# DoXe_7SEG_Arduino.net
KiCad netlist of a schematic drawn in Altium Designer
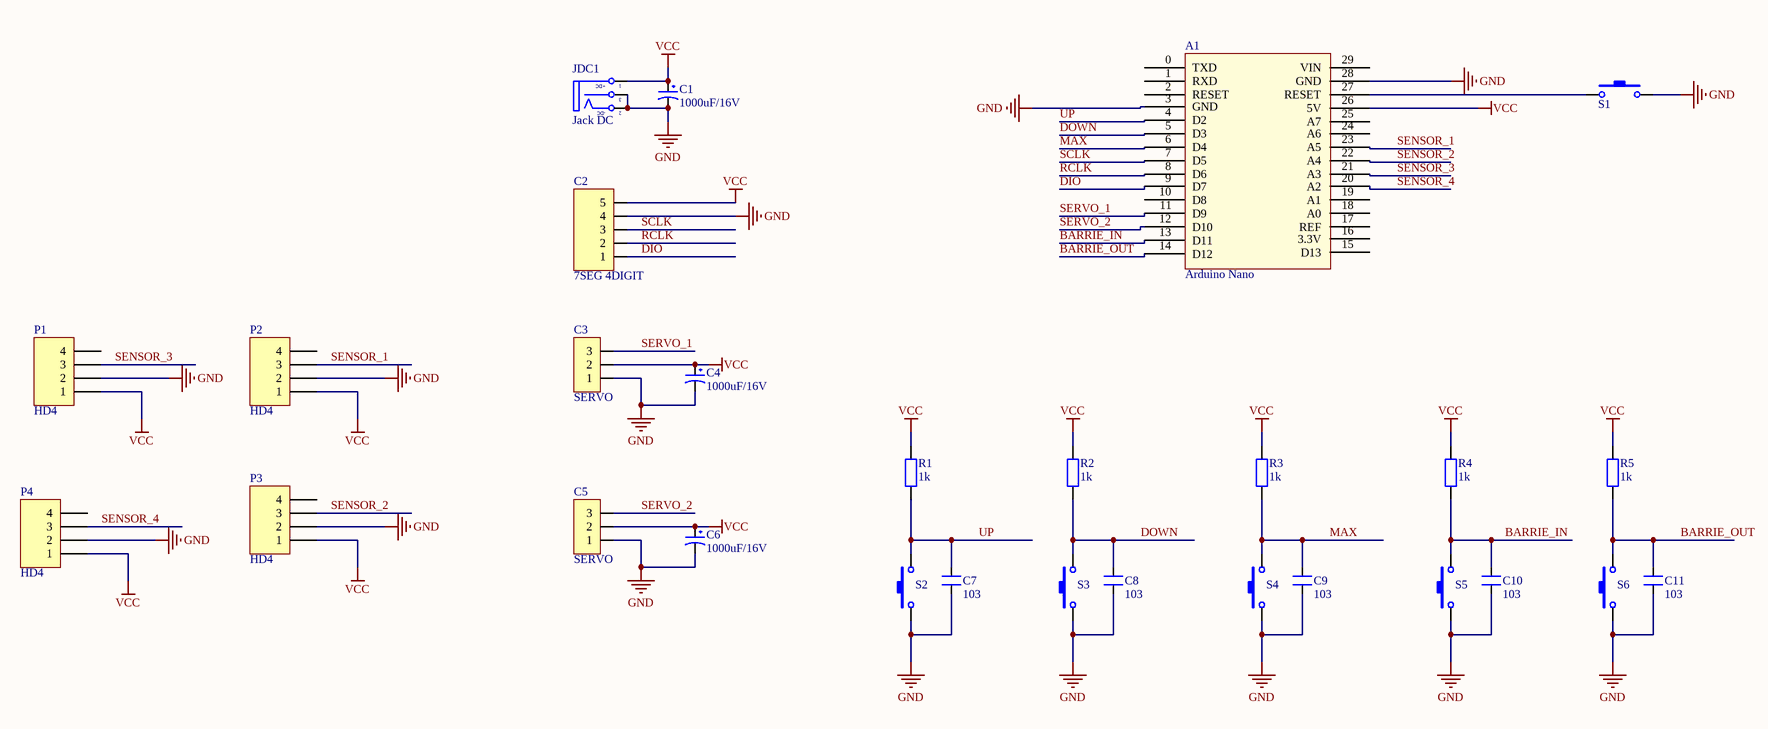
[diagram p0: DoXe_7SEG_Arduino.SchDoc]

(export (version "E")
  (design (tool "Eeschema 10.0.6"))
  (components
    (comp (ref "A1")
      (value "Arduino Nano")
      (footprint "Arduino Nano_JUMP")
      (libsource (lib "OBIT_TESLA") (part "Arduino Nano"))
    )
    (comp (ref "C1")
      (value "1000uF/16V")
      (footprint "CP1.5/3.4")
      (description "Cap 1000uF/16V - 220uF/50V")
      (libsource (lib "OBIT_TESLA") (part "CP4"))
    )
    (comp (ref "C2")
      (value "7SEG 4DIGIT")
      (footprint "JP5-D1T")
      (description "WR-PHD 2.54 mm Angled Socket Header")
      (fields
        (field (name "MANUFACTURER") "Würth Elektronik eiSos GmbH")
        (field (name "PARTNO") "613005143121")
        (field (name "CREATED BY") "Karrer Zheng")
      )
      (libsource (lib "OBIT_TESLA") (part "JP5"))
    )
    (comp (ref "C3")
      (value "SERVO")
      (footprint "JP3-D1T")
      (description "WR-PHD 2.54 mm Angled Socket Header")
      (fields
        (field (name "MANUFACTURER") "Würth Elektronik eiSos GmbH")
        (field (name "PARTNO") "613003143121")
        (field (name "CREATED BY") "Karrer Zheng")
      )
      (libsource (lib "OBIT_TESLA") (part "JP3"))
    )
    (comp (ref "C4")
      (value "1000uF/16V")
      (footprint "CP1.5/3.4")
      (description "Cap 1000uF/16V - 220uF/50V")
      (libsource (lib "OBIT_TESLA") (part "CP4"))
    )
    (comp (ref "C5")
      (value "SERVO")
      (footprint "JP3-D1T")
      (description "WR-PHD 2.54 mm Angled Socket Header")
      (fields
        (field (name "MANUFACTURER") "Würth Elektronik eiSos GmbH")
        (field (name "PARTNO") "613003143121")
        (field (name "CREATED BY") "Karrer Zheng")
      )
      (libsource (lib "OBIT_TESLA") (part "JP3"))
    )
    (comp (ref "C6")
      (value "1000uF/16V")
      (footprint "CP1.5/3.4")
      (description "Cap 1000uF/16V - 220uF/50V")
      (libsource (lib "OBIT_TESLA") (part "CP4"))
    )
    (comp (ref "C7")
      (value "103")
      (footprint "SM-0805")
      (description "Cap SMD")
      (libsource (lib "OBIT_TESLA") (part "CM"))
    )
    (comp (ref "C8")
      (value "103")
      (footprint "SM-0805")
      (description "Cap SMD")
      (libsource (lib "OBIT_TESLA") (part "CM"))
    )
    (comp (ref "C9")
      (value "103")
      (footprint "SM-0805")
      (description "Cap SMD")
      (libsource (lib "OBIT_TESLA") (part "CM"))
    )
    (comp (ref "C10")
      (value "103")
      (footprint "SM-0805")
      (description "Cap SMD")
      (libsource (lib "OBIT_TESLA") (part "CM"))
    )
    (comp (ref "C11")
      (value "103")
      (footprint "SM-0805")
      (description "Cap SMD")
      (libsource (lib "OBIT_TESLA") (part "CM"))
    )
    (comp (ref "JDC1") (value "Jack DC") (footprint "DC0") (libsource (lib "OBIT_TESLA") (part "JACK_DC")))
    (comp (ref "P1") (value "HD4") (footprint "HEADER 4") (libsource (lib "OBIT_TESLA") (part "HEADER 4")))
    (comp (ref "P2") (value "HD4") (footprint "HEADER 4") (libsource (lib "OBIT_TESLA") (part "HEADER 4")))
    (comp (ref "P3") (value "HD4") (footprint "HEADER 4") (libsource (lib "OBIT_TESLA") (part "HEADER 4")))
    (comp (ref "P4") (value "HD4") (footprint "HEADER 4") (libsource (lib "OBIT_TESLA") (part "HEADER 4")))
    (comp (ref "R1")
      (value "1k")
      (footprint "RES-1/4W")
      (description "Resistor R1/4W")
      (libsource (lib "OBIT_TESLA") (part "R"))
    )
    (comp (ref "R2")
      (value "1k")
      (footprint "RES-1/4W")
      (description "Resistor R1/4W")
      (libsource (lib "OBIT_TESLA") (part "R"))
    )
    (comp (ref "R3")
      (value "1k")
      (footprint "RES-1/4W")
      (description "Resistor R1/4W")
      (libsource (lib "OBIT_TESLA") (part "R"))
    )
    (comp (ref "R4")
      (value "1k")
      (footprint "RES-1/4W")
      (description "Resistor R1/4W")
      (libsource (lib "OBIT_TESLA") (part "R"))
    )
    (comp (ref "R5")
      (value "1k")
      (footprint "RES-1/4W")
      (description "Resistor R1/4W")
      (libsource (lib "OBIT_TESLA") (part "R"))
    )
    (comp (ref "S1")
      (value "SW")
      (footprint "BUTTON  ROUND")
      (description "Switch-Button")
      (fields (field (name "PUBLISHER") "Altium Limited"))
      (libsource (lib "OBIT_TESLA") (part "SW-Button"))
    )
    (comp (ref "S2")
      (value "SW")
      (footprint "BUTTON  ROUND")
      (description "Switch-Button")
      (fields (field (name "PUBLISHER") "Altium Limited"))
      (libsource (lib "OBIT_TESLA") (part "SW-Button"))
    )
    (comp (ref "S3")
      (value "SW")
      (footprint "BUTTON  ROUND")
      (description "Switch-Button")
      (fields (field (name "PUBLISHER") "Altium Limited"))
      (libsource (lib "OBIT_TESLA") (part "SW-Button"))
    )
    (comp (ref "S4")
      (value "SW")
      (footprint "BUTTON  ROUND")
      (description "Switch-Button")
      (fields (field (name "PUBLISHER") "Altium Limited"))
      (libsource (lib "OBIT_TESLA") (part "SW-Button"))
    )
    (comp (ref "S5")
      (value "SW")
      (footprint "BUTTON  ROUND")
      (description "Switch-Button")
      (fields (field (name "PUBLISHER") "Altium Limited"))
      (libsource (lib "OBIT_TESLA") (part "SW-Button"))
    )
    (comp (ref "S6")
      (value "SW")
      (footprint "BUTTON  ROUND")
      (description "Switch-Button")
      (fields (field (name "PUBLISHER") "Altium Limited"))
      (libsource (lib "OBIT_TESLA") (part "SW-Button"))
    )
  )
  (nets
    (net (code "1") (name "/BARRIE_IN") (class "Default")
      (node (ref "A1") (pin "13") (pinfunction "D11_13") (pintype "passive"))
      (node (ref "C10") (pin "2") (pinfunction "2_2") (pintype "passive"))
      (node (ref "R4") (pin "1") (pinfunction "1_1") (pintype "passive"))
      (node (ref "S5") (pin "2") (pinfunction "2_2") (pintype "passive"))
    )
    (net (code "2") (name "/BARRIE_OUT") (class "Default")
      (node (ref "A1") (pin "14") (pinfunction "D12_14") (pintype "passive"))
      (node (ref "C11") (pin "2") (pinfunction "2_2") (pintype "passive"))
      (node (ref "R5") (pin "1") (pinfunction "1_1") (pintype "passive"))
      (node (ref "S6") (pin "2") (pinfunction "2_2") (pintype "passive"))
    )
    (net (code "3") (name "/DIO") (class "Default")
      (node (ref "A1") (pin "9") (pinfunction "D7_9") (pintype "passive"))
      (node (ref "C2") (pin "1") (pinfunction "1_1") (pintype "passive"))
    )
    (net (code "4") (name "/DOWN") (class "Default")
      (node (ref "A1") (pin "5") (pinfunction "D3_5") (pintype "passive"))
      (node (ref "C8") (pin "2") (pinfunction "2_2") (pintype "passive"))
      (node (ref "R2") (pin "1") (pinfunction "1_1") (pintype "passive"))
      (node (ref "S3") (pin "2") (pinfunction "2_2") (pintype "passive"))
    )
    (net (code "5") (name "/MAX") (class "Default")
      (node (ref "A1") (pin "6") (pinfunction "D4_6") (pintype "passive"))
      (node (ref "C9") (pin "2") (pinfunction "2_2") (pintype "passive"))
      (node (ref "R3") (pin "1") (pinfunction "1_1") (pintype "passive"))
      (node (ref "S4") (pin "2") (pinfunction "2_2") (pintype "passive"))
    )
    (net (code "6") (name "/RCLK") (class "Default")
      (node (ref "A1") (pin "8") (pinfunction "D6_8") (pintype "passive"))
      (node (ref "C2") (pin "2") (pinfunction "2_2") (pintype "passive"))
    )
    (net (code "7") (name "/SCLK") (class "Default")
      (node (ref "A1") (pin "7") (pinfunction "D5_7") (pintype "passive"))
      (node (ref "C2") (pin "3") (pinfunction "3_3") (pintype "passive"))
    )
    (net (code "8") (name "/SENSOR_1") (class "Default")
      (node (ref "A1") (pin "23") (pinfunction "A5_23") (pintype "passive"))
      (node (ref "P2") (pin "3") (pinfunction "3_3") (pintype "passive"))
    )
    (net (code "9") (name "/SENSOR_2") (class "Default")
      (node (ref "A1") (pin "22") (pinfunction "A4_22") (pintype "passive"))
      (node (ref "P3") (pin "3") (pinfunction "3_3") (pintype "passive"))
    )
    (net (code "10") (name "/SENSOR_3") (class "Default")
      (node (ref "A1") (pin "21") (pinfunction "A3_21") (pintype "passive"))
      (node (ref "P1") (pin "3") (pinfunction "3_3") (pintype "passive"))
    )
    (net (code "11") (name "/SENSOR_4") (class "Default")
      (node (ref "A1") (pin "20") (pinfunction "A2_20") (pintype "passive"))
      (node (ref "P4") (pin "3") (pinfunction "3_3") (pintype "passive"))
    )
    (net (code "12") (name "/SERVO_1") (class "Default")
      (node (ref "A1") (pin "11") (pinfunction "D9_11") (pintype "passive"))
      (node (ref "C3") (pin "3") (pinfunction "3_3") (pintype "passive"))
    )
    (net (code "13") (name "/SERVO_2") (class "Default")
      (node (ref "A1") (pin "12") (pinfunction "D10_12") (pintype "passive"))
      (node (ref "C5") (pin "3") (pinfunction "3_3") (pintype "passive"))
    )
    (net (code "14") (name "/UP") (class "Default")
      (node (ref "A1") (pin "4") (pinfunction "D2_4") (pintype "passive"))
      (node (ref "C7") (pin "2") (pinfunction "2_2") (pintype "passive"))
      (node (ref "R1") (pin "1") (pinfunction "1_1") (pintype "passive"))
      (node (ref "S2") (pin "2") (pinfunction "2_2") (pintype "passive"))
    )
    (net (code "15") (name "GND") (class "Default")
      (node (ref "A1") (pin "28") (pinfunction "GND_28") (pintype "passive"))
      (node (ref "A1") (pin "3") (pinfunction "GND_3") (pintype "passive"))
      (node (ref "C1") (pin "2") (pinfunction "2_2") (pintype "passive"))
      (node (ref "C10") (pin "1") (pinfunction "1_1") (pintype "passive"))
      (node (ref "C11") (pin "1") (pinfunction "1_1") (pintype "passive"))
      (node (ref "C2") (pin "4") (pinfunction "4_4") (pintype "passive"))
      (node (ref "C3") (pin "1") (pinfunction "1_1") (pintype "passive"))
      (node (ref "C4") (pin "2") (pinfunction "2_2") (pintype "passive"))
      (node (ref "C5") (pin "1") (pinfunction "1_1") (pintype "passive"))
      (node (ref "C6") (pin "2") (pinfunction "2_2") (pintype "passive"))
      (node (ref "C7") (pin "1") (pinfunction "1_1") (pintype "passive"))
      (node (ref "C8") (pin "1") (pinfunction "1_1") (pintype "passive"))
      (node (ref "C9") (pin "1") (pinfunction "1_1") (pintype "passive"))
      (node (ref "JDC1") (pin "2") (pinfunction "TN_2") (pintype "passive"))
      (node (ref "JDC1") (pin "3") (pinfunction "S_3") (pintype "power_in"))
      (node (ref "P1") (pin "2") (pinfunction "2_2") (pintype "passive"))
      (node (ref "P2") (pin "2") (pinfunction "2_2") (pintype "passive"))
      (node (ref "P3") (pin "2") (pinfunction "2_2") (pintype "passive"))
      (node (ref "P4") (pin "2") (pinfunction "2_2") (pintype "passive"))
      (node (ref "S1") (pin "2") (pinfunction "2_2") (pintype "passive"))
      (node (ref "S2") (pin "1") (pinfunction "1_1") (pintype "passive"))
      (node (ref "S3") (pin "1") (pinfunction "1_1") (pintype "passive"))
      (node (ref "S4") (pin "1") (pinfunction "1_1") (pintype "passive"))
      (node (ref "S5") (pin "1") (pinfunction "1_1") (pintype "passive"))
      (node (ref "S6") (pin "1") (pinfunction "1_1") (pintype "passive"))
    )
    (net (code "16") (name "Net-(A1-RESET-Pad27)") (class "Default")
      (node (ref "A1") (pin "27") (pinfunction "RESET_27") (pintype "passive"))
      (node (ref "S1") (pin "1") (pinfunction "1_1") (pintype "passive"))
    )
    (net (code "17") (name "VCC") (class "Default")
      (node (ref "A1") (pin "26") (pinfunction "5V_26") (pintype "passive"))
      (node (ref "C1") (pin "1") (pinfunction "1_1") (pintype "passive"))
      (node (ref "C2") (pin "5") (pinfunction "5_5") (pintype "passive"))
      (node (ref "C3") (pin "2") (pinfunction "2_2") (pintype "passive"))
      (node (ref "C4") (pin "1") (pinfunction "1_1") (pintype "passive"))
      (node (ref "C5") (pin "2") (pinfunction "2_2") (pintype "passive"))
      (node (ref "C6") (pin "1") (pinfunction "1_1") (pintype "passive"))
      (node (ref "JDC1") (pin "1") (pinfunction "T_1") (pintype "passive"))
      (node (ref "P1") (pin "1") (pinfunction "1_1") (pintype "passive"))
      (node (ref "P2") (pin "1") (pinfunction "1_1") (pintype "passive"))
      (node (ref "P3") (pin "1") (pinfunction "1_1") (pintype "passive"))
      (node (ref "P4") (pin "1") (pinfunction "1_1") (pintype "passive"))
      (node (ref "R1") (pin "2") (pinfunction "2_2") (pintype "passive"))
      (node (ref "R2") (pin "2") (pinfunction "2_2") (pintype "passive"))
      (node (ref "R3") (pin "2") (pinfunction "2_2") (pintype "passive"))
      (node (ref "R4") (pin "2") (pinfunction "2_2") (pintype "passive"))
      (node (ref "R5") (pin "2") (pinfunction "2_2") (pintype "passive"))
    )
    (net (code "18") (name "unconnected-(A1-3.3V-Pad16)") (class "Default")
      (node (ref "A1") (pin "16") (pinfunction "3.3V_16") (pintype "passive"))
    )
    (net (code "19") (name "unconnected-(A1-A0-Pad18)") (class "Default")
      (node (ref "A1") (pin "18") (pinfunction "A0_18") (pintype "passive"))
    )
    (net (code "20") (name "unconnected-(A1-A1-Pad19)") (class "Default")
      (node (ref "A1") (pin "19") (pinfunction "A1_19") (pintype "passive"))
    )
    (net (code "21") (name "unconnected-(A1-A6-Pad24)") (class "Default")
      (node (ref "A1") (pin "24") (pinfunction "A6_24") (pintype "passive"))
    )
    (net (code "22") (name "unconnected-(A1-A7-Pad25)") (class "Default")
      (node (ref "A1") (pin "25") (pinfunction "A7_25") (pintype "passive"))
    )
    (net (code "23") (name "unconnected-(A1-D8-Pad10)") (class "Default")
      (node (ref "A1") (pin "10") (pinfunction "D8_10") (pintype "passive"))
    )
    (net (code "24") (name "unconnected-(A1-D13-Pad15)") (class "Default")
      (node (ref "A1") (pin "15") (pinfunction "D13_15") (pintype "passive"))
    )
    (net (code "25") (name "unconnected-(A1-REF-Pad17)") (class "Default")
      (node (ref "A1") (pin "17") (pinfunction "REF_17") (pintype "passive"))
    )
    (net (code "26") (name "unconnected-(A1-RESET-Pad2)") (class "Default")
      (node (ref "A1") (pin "2") (pinfunction "RESET_2") (pintype "passive"))
    )
    (net (code "27") (name "unconnected-(A1-RXD-Pad1)") (class "Default")
      (node (ref "A1") (pin "1") (pinfunction "RXD_1") (pintype "passive"))
    )
    (net (code "28") (name "unconnected-(A1-TXD-Pad0)") (class "Default")
      (node (ref "A1") (pin "0") (pinfunction "TXD_0") (pintype "passive"))
    )
    (net (code "29") (name "unconnected-(A1-VIN-Pad29)") (class "Default")
      (node (ref "A1") (pin "29") (pinfunction "VIN_29") (pintype "passive"))
    )
    (net (code "30") (name "unconnected-(P1-Pad4)") (class "Default")
      (node (ref "P1") (pin "4") (pinfunction "4_4") (pintype "passive"))
    )
    (net (code "31") (name "unconnected-(P2-Pad4)") (class "Default")
      (node (ref "P2") (pin "4") (pinfunction "4_4") (pintype "passive"))
    )
    (net (code "32") (name "unconnected-(P3-Pad4)") (class "Default")
      (node (ref "P3") (pin "4") (pinfunction "4_4") (pintype "passive"))
    )
    (net (code "33") (name "unconnected-(P4-Pad4)") (class "Default")
      (node (ref "P4") (pin "4") (pinfunction "4_4") (pintype "passive"))
    )
  )
)
